# EP.net
KiCad netlist of a schematic drawn in Altium Designer
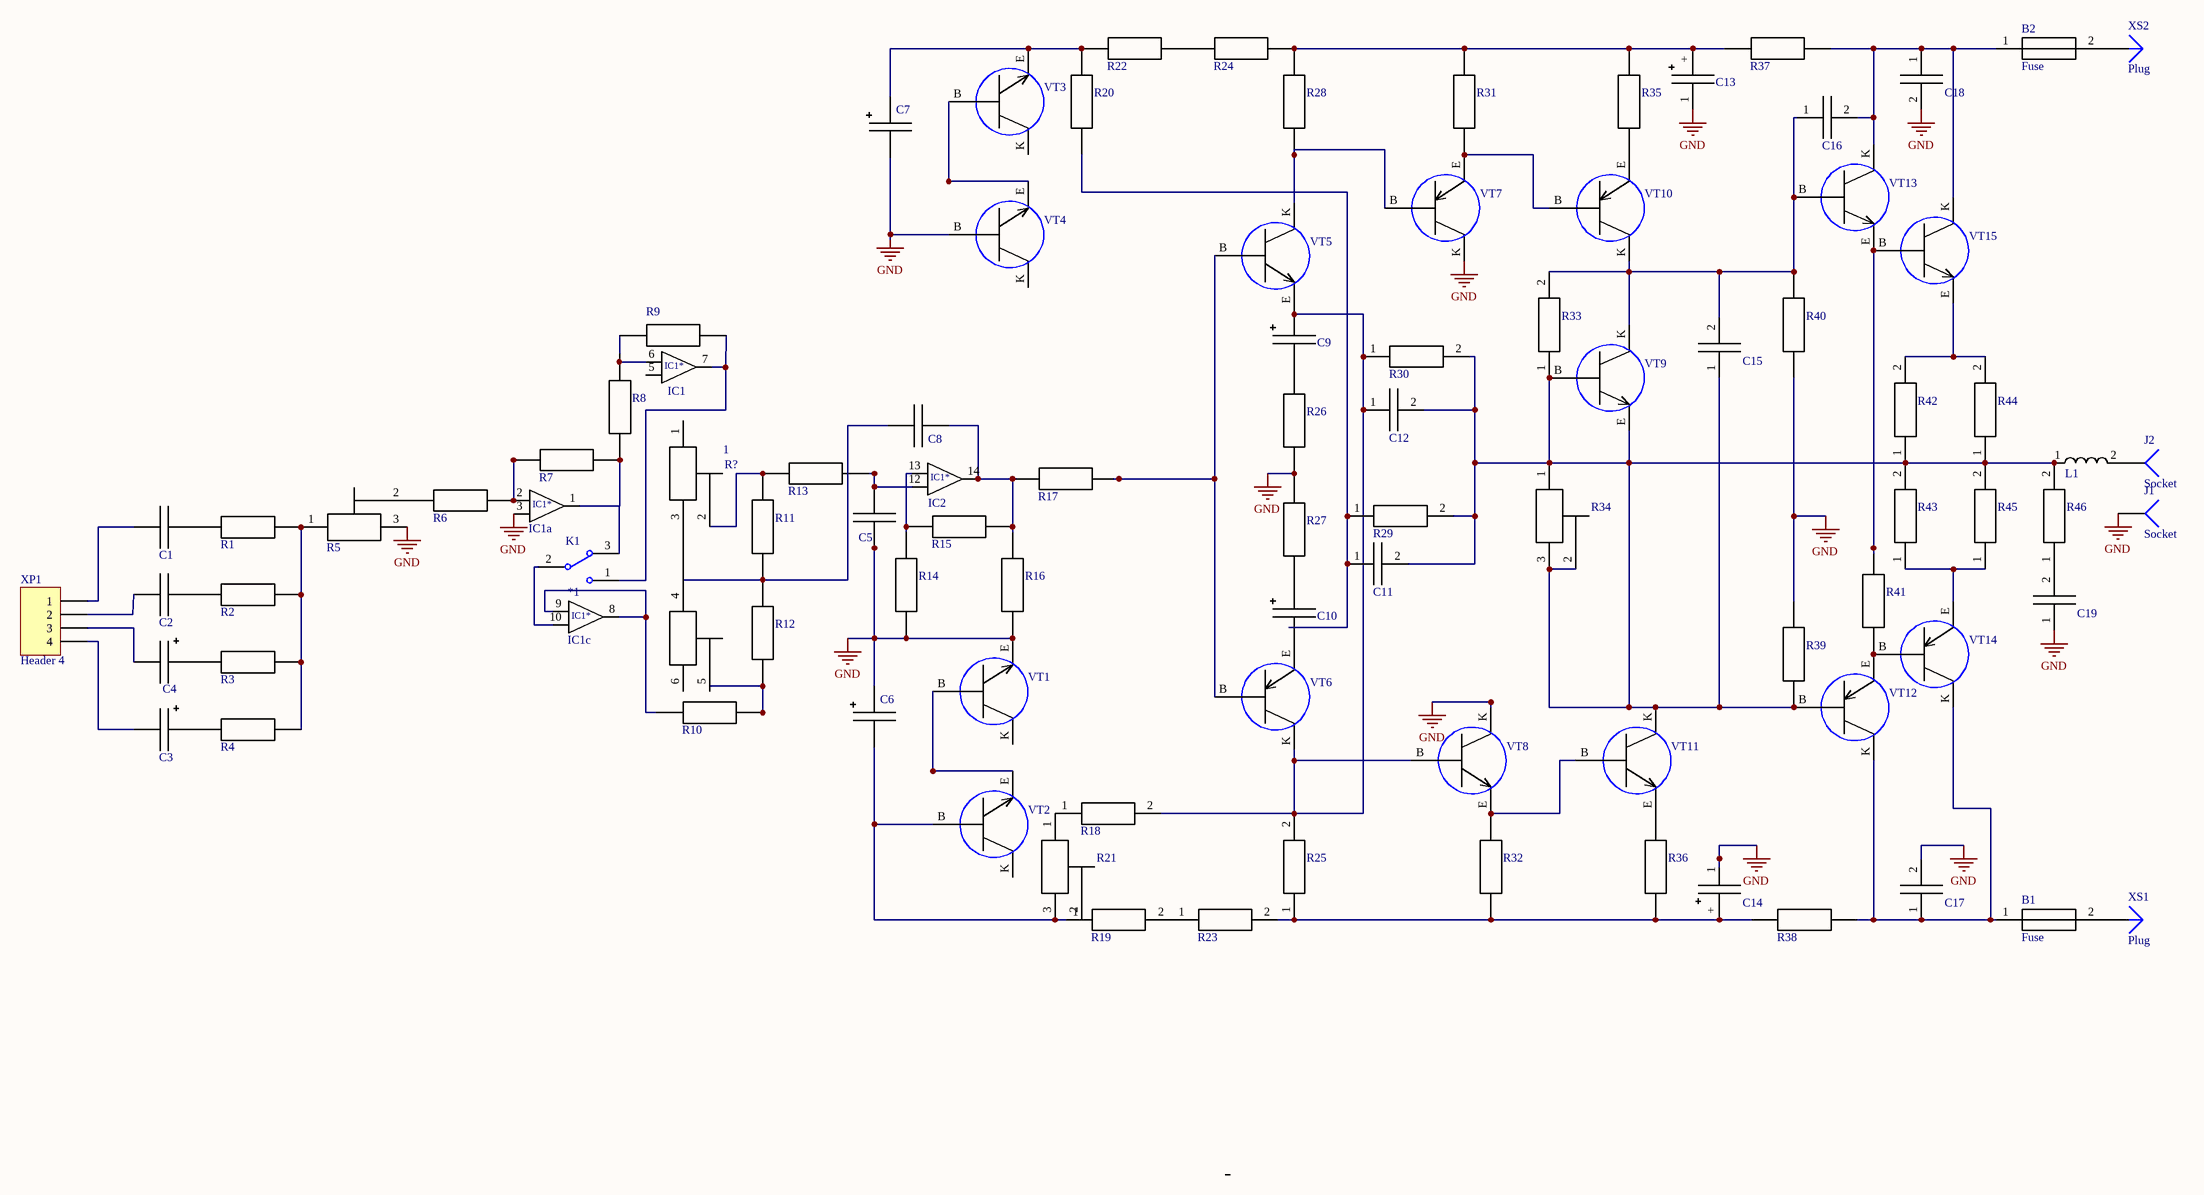
[diagram p0: EP.SchDoc]

(export (version "E")
  (design (tool "Eeschema 10.0.6"))
  (components
    (comp (ref "*1") (value "IC1c") (footprint "DIP8") (libsource (lib "Schlib2") (part "TL084")))
    (comp (ref "1")
      (value "R?")
      (footprint "PcbLib2:Pidresistor")
      (libsource (lib "Schlib2") (part "Pidres_2"))
    )
    (comp (ref "B1") (value "Fuse") (libsource (lib "Schlib2") (part "Fuse")))
    (comp (ref "B2") (value "Fuse") (libsource (lib "Schlib2") (part "Fuse")))
    (comp (ref "C1") (value "Capacitor") (footprint "Capacitor") (libsource (lib "") (part "Capacitor_1")))
    (comp (ref "C2") (value "Capacitor") (footprint "Capacitor") (libsource (lib "") (part "Capacitor_1")))
    (comp (ref "C3")
      (value "Capacitor (+)")
      (footprint "Capacitor (+) 2.5")
      (libsource (lib "Schlib2") (part "Capacitor (+)"))
    )
    (comp (ref "C4")
      (value "Capacitor (+)")
      (footprint "Capacitor (+) 2.5")
      (libsource (lib "Schlib2") (part "Capacitor (+)"))
    )
    (comp (ref "C5") (value "Capacitor") (footprint "Capacitor") (libsource (lib "") (part "Capacitor_1")))
    (comp (ref "C6")
      (value "Capacitor (+)")
      (footprint "Capacitor (+) 2.5")
      (libsource (lib "Schlib2") (part "Capacitor (+)"))
    )
    (comp (ref "C7")
      (value "Capacitor (+)")
      (footprint "Capacitor (+) 2.5")
      (libsource (lib "Schlib2") (part "Capacitor (+)"))
    )
    (comp (ref "C8") (value "Capacitor") (footprint "Capacitor") (libsource (lib "") (part "Capacitor_1")))
    (comp (ref "C9")
      (value "Capacitor (+)")
      (footprint "Capacitor (+) 2.5")
      (libsource (lib "Schlib2") (part "Capacitor (+)"))
    )
    (comp (ref "C10")
      (value "Capacitor (+)")
      (footprint "Capacitor (+) 2.5")
      (libsource (lib "Schlib2") (part "Capacitor (+)"))
    )
    (comp (ref "C11")
      (value "Capacitor")
      (footprint "Capacitor")
      (libsource (lib "Schlib2") (part "Capacitor"))
    )
    (comp (ref "C12")
      (value "Capacitor")
      (footprint "Capacitor")
      (libsource (lib "Schlib2") (part "Capacitor"))
    )
    (comp (ref "C13")
      (value "Capacitor (+)")
      (footprint "Capacitor (+) 2.5")
      (libsource (lib "") (part "Capacitor (+)_1"))
    )
    (comp (ref "C14")
      (value "Capacitor (+)")
      (footprint "Capacitor (+) 2.5")
      (libsource (lib "") (part "Capacitor (+)_1"))
    )
    (comp (ref "C15")
      (value "Capacitor")
      (footprint "Capacitor")
      (libsource (lib "Schlib2") (part "Capacitor"))
    )
    (comp (ref "C16")
      (value "Capacitor")
      (footprint "Capacitor")
      (libsource (lib "Schlib2") (part "Capacitor"))
    )
    (comp (ref "C17")
      (value "Capacitor")
      (footprint "Capacitor")
      (libsource (lib "Schlib2") (part "Capacitor"))
    )
    (comp (ref "C18")
      (value "Capacitor")
      (footprint "Capacitor")
      (libsource (lib "Schlib2") (part "Capacitor"))
    )
    (comp (ref "C19")
      (value "Capacitor")
      (footprint "Capacitor")
      (libsource (lib "Schlib2") (part "Capacitor"))
    )
    (comp (ref "IC1") (value "TL084") (footprint "DIP8") (libsource (lib "") (part "TL084_3")))
    (comp (ref "IC1a") (value "IC1a") (footprint "DIP8") (libsource (lib "") (part "TL084_2")))
    (comp (ref "IC2") (value "IC1d") (footprint "DIP8") (libsource (lib "") (part "TL084_1")))
    (comp (ref "J1")
      (value "Socket")
      (footprint "PIN1")
      (fields (field (name "PUBLISHER") "Altium Limited"))
      (libsource (lib "Miscellaneous Connectors") (part "Socket"))
    )
    (comp (ref "J2")
      (value "Socket")
      (footprint "PIN1")
      (fields (field (name "PUBLISHER") "Altium Limited"))
      (libsource (lib "Miscellaneous Connectors") (part "Socket"))
    )
    (comp (ref "K1")
      (value "K")
      (footprint "TL36WW15050")
      (description "SPDT Subminiature Toggle Switch, Right Angle Mounting, Vertical Actuation")
      (fields (field (name "PUBLISHER") "Altium Limited"))
      (libsource (lib "Miscellaneous Devices") (part "SW-SPDT"))
    )
    (comp (ref "L1") (value "Drosel") (footprint "Drosel") (libsource (lib "Schlib2") (part "Drosel")))
    (comp (ref "R1") (value "Resistor") (footprint "Resistor") (libsource (lib "Schlib2") (part "Resistor")))
    (comp (ref "R2") (value "Resistor") (footprint "Resistor") (libsource (lib "Schlib2") (part "Resistor")))
    (comp (ref "R3") (value "Resistor") (footprint "Resistor") (libsource (lib "Schlib2") (part "Resistor")))
    (comp (ref "R4") (value "Resistor") (footprint "Resistor") (libsource (lib "Schlib2") (part "Resistor")))
    (comp (ref "R5")
      (value "Pidresistor")
      (footprint "Pidrest_2")
      (libsource (lib "Schlib2") (part "Pidresistor"))
    )
    (comp (ref "R6") (value "Resistor") (footprint "Resistor") (libsource (lib "Schlib2") (part "Resistor")))
    (comp (ref "R7") (value "Resistor") (footprint "Resistor") (libsource (lib "Schlib2") (part "Resistor")))
    (comp (ref "R8") (value "Resistor") (footprint "Resistor") (libsource (lib "Schlib2") (part "Resistor")))
    (comp (ref "R9") (value "Resistor") (footprint "Resistor") (libsource (lib "Schlib2") (part "Resistor")))
    (comp (ref "R10") (value "Resistor") (footprint "Resistor") (libsource (lib "Schlib2") (part "Resistor")))
    (comp (ref "R11") (value "Resistor") (footprint "Resistor") (libsource (lib "Schlib2") (part "Resistor")))
    (comp (ref "R12") (value "Resistor") (footprint "Resistor") (libsource (lib "Schlib2") (part "Resistor")))
    (comp (ref "R13") (value "Resistor") (footprint "Resistor") (libsource (lib "Schlib2") (part "Resistor")))
    (comp (ref "R14") (value "Resistor") (footprint "Resistor") (libsource (lib "Schlib2") (part "Resistor")))
    (comp (ref "R15") (value "Resistor") (footprint "Resistor") (libsource (lib "Schlib2") (part "Resistor")))
    (comp (ref "R16") (value "Resistor") (footprint "Resistor") (libsource (lib "Schlib2") (part "Resistor")))
    (comp (ref "R17") (value "Resistor") (footprint "Resistor") (libsource (lib "Schlib2") (part "Resistor")))
    (comp (ref "R18") (value "Resistor") (footprint "Resistor") (libsource (lib "") (part "Resistor_1")))
    (comp (ref "R19") (value "Resistor") (footprint "Resistor") (libsource (lib "") (part "Resistor_1")))
    (comp (ref "R20") (value "Resistor") (footprint "Resistor") (libsource (lib "Schlib2") (part "Resistor")))
    (comp (ref "R21")
      (value "Pidresistor")
      (footprint "Pidresistor")
      (libsource (lib "Schlib2") (part "Pidresistor"))
    )
    (comp (ref "R22") (value "Resistor") (footprint "Resistor") (libsource (lib "Schlib2") (part "Resistor")))
    (comp (ref "R23") (value "Resistor") (footprint "Resistor") (libsource (lib "") (part "Resistor_1")))
    (comp (ref "R24") (value "Resistor") (footprint "Resistor") (libsource (lib "Schlib2") (part "Resistor")))
    (comp (ref "R25") (value "Resistor") (footprint "Resistor") (libsource (lib "") (part "Resistor_1")))
    (comp (ref "R26") (value "Resistor") (footprint "Resistor") (libsource (lib "Schlib2") (part "Resistor")))
    (comp (ref "R27") (value "Resistor") (footprint "Resistor") (libsource (lib "Schlib2") (part "Resistor")))
    (comp (ref "R28") (value "Resistor") (footprint "Resistor") (libsource (lib "Schlib2") (part "Resistor")))
    (comp (ref "R29") (value "Resistor") (footprint "Resistor") (libsource (lib "") (part "Resistor_1")))
    (comp (ref "R30") (value "Resistor") (footprint "Resistor") (libsource (lib "") (part "Resistor_1")))
    (comp (ref "R31") (value "Resistor") (footprint "Resistor") (libsource (lib "Schlib2") (part "Resistor")))
    (comp (ref "R32") (value "Resistor") (footprint "Resistor") (libsource (lib "Schlib2") (part "Resistor")))
    (comp (ref "R33") (value "Resistor") (footprint "Resistor") (libsource (lib "") (part "Resistor_1")))
    (comp (ref "R34")
      (value "Pidresistor")
      (footprint "Pidresistor")
      (libsource (lib "Schlib2") (part "Pidresistor"))
    )
    (comp (ref "R35") (value "Resistor") (footprint "Resistor") (libsource (lib "Schlib2") (part "Resistor")))
    (comp (ref "R36") (value "Resistor") (footprint "Resistor") (libsource (lib "Schlib2") (part "Resistor")))
    (comp (ref "R37") (value "Resistor") (footprint "Resistor") (libsource (lib "Schlib2") (part "Resistor")))
    (comp (ref "R38") (value "Resistor") (footprint "Resistor") (libsource (lib "Schlib2") (part "Resistor")))
    (comp (ref "R39") (value "Resistor") (footprint "Resistor") (libsource (lib "Schlib2") (part "Resistor")))
    (comp (ref "R40") (value "Resistor") (footprint "Resistor") (libsource (lib "Schlib2") (part "Resistor")))
    (comp (ref "R41") (value "Resistor") (footprint "Resistor") (libsource (lib "Schlib2") (part "Resistor")))
    (comp (ref "R42")
      (value "Resistor 1 Wt")
      (footprint "Resistor 1 Wt")
      (libsource (lib "Schlib2") (part "Resistor 1 Wt"))
    )
    (comp (ref "R43")
      (value "Resistor 1 Wt")
      (footprint "Resistor 1 Wt")
      (libsource (lib "Schlib2") (part "Resistor 1 Wt"))
    )
    (comp (ref "R44")
      (value "Resistor 1 Wt")
      (footprint "Resistor 1 Wt")
      (libsource (lib "Schlib2") (part "Resistor 1 Wt"))
    )
    (comp (ref "R45")
      (value "Resistor 1 Wt")
      (footprint "Resistor 1 Wt")
      (libsource (lib "Schlib2") (part "Resistor 1 Wt"))
    )
    (comp (ref "R46")
      (value "Resistor 1 Wt")
      (footprint "Resistor 1 Wt")
      (libsource (lib "Schlib2") (part "Resistor 1 Wt"))
    )
    (comp (ref "VT1") (value "卵238;639;") (footprint "TO-92") (libsource (lib "") (part "卵238;639;_1")))
    (comp (ref "VT2") (value "卵238;639;") (footprint "TO-92") (libsource (lib "") (part "卵238;639;_1")))
    (comp (ref "VT3") (value "卵238;639;") (footprint "TO-92") (libsource (lib "") (part "卵238;639;_1")))
    (comp (ref "VT4") (value "卵238;639;") (footprint "TO-92") (libsource (lib "") (part "卵238;639;_1")))
    (comp (ref "VT5") (value "卵238;639;") (footprint "TO-92") (libsource (lib "Schlib2") (part "卵238;639;")))
    (comp (ref "VT6") (value "卵640") (footprint "TO-92") (libsource (lib "Schlib2") (part "卵640")))
    (comp (ref "VT7") (value "卵640") (footprint "TO-92") (libsource (lib "Schlib2") (part "卵640")))
    (comp (ref "VT8") (value "卵238;639;") (footprint "TO-92") (libsource (lib "Schlib2") (part "卵238;639;")))
    (comp (ref "VT9")
      (value "MJE340")
      (footprint "TO-126(TO-225)")
      (libsource (lib "Schlib2") (part "MJE340"))
    )
    (comp (ref "VT10")
      (value "MJE350")
      (footprint "TO-126(TO-225)")
      (libsource (lib "Schlib2") (part "MJE350"))
    )
    (comp (ref "VT11")
      (value "BD137")
      (footprint "TO-126(TO-225)")
      (libsource (lib "Schlib2") (part "BD137"))
    )
    (comp (ref "VT12") (value "BD242C") (footprint "TO-220") (libsource (lib "Schlib2") (part "BD242C")))
    (comp (ref "VT13") (value "BD241C") (footprint "TO-220") (libsource (lib "Schlib2") (part "BD241C")))
    (comp (ref "VT14") (value "BD250C") (footprint "TO-220") (libsource (lib "Schlib2") (part "BD250C")))
    (comp (ref "VT15") (value "BD249C") (footprint "SOT-93") (libsource (lib "Schlib2") (part "BD249C")))
    (comp (ref "XP1")
      (value "Header 4")
      (footprint "HDR1X4")
      (description "Header, 4-Pin")
      (fields (field (name "PUBLISHER") "Altium Limited"))
      (libsource (lib "Miscellaneous Connectors") (part "Header 4"))
    )
    (comp (ref "XS1")
      (value "Plug")
      (footprint "PIN1")
      (fields (field (name "PUBLISHER") "Altium Limited"))
      (libsource (lib "Miscellaneous Connectors") (part "Plug"))
    )
    (comp (ref "XS2")
      (value "Plug")
      (footprint "PIN1")
      (fields (field (name "PUBLISHER") "Altium Limited"))
      (libsource (lib "Miscellaneous Connectors") (part "Plug"))
    )
  )
  (nets
    (net (code "1") (name "GND") (class "Default")
      (node (ref "C13") (pin "1") (pinfunction "1_1") (pintype "passive"))
      (node (ref "C14") (pin "1") (pinfunction "1_1") (pintype "passive"))
      (node (ref "C17") (pin "2") (pinfunction "2_2") (pintype "passive"))
      (node (ref "C18") (pin "2") (pinfunction "2_2") (pintype "passive"))
      (node (ref "C19") (pin "1") (pinfunction "1_1") (pintype "passive"))
      (node (ref "C5") (pin "2") (pinfunction "2_2") (pintype "passive"))
      (node (ref "C6") (pin "+") (pinfunction "+_+") (pintype "passive"))
      (node (ref "C7") (pin "1") (pinfunction "1_1") (pintype "passive"))
      (node (ref "IC1a") (pin "3") (pinfunction "3_3") (pintype "passive"))
      (node (ref "J1") (pin "1") (pinfunction "1_1") (pintype "passive"))
      (node (ref "R14") (pin "2") (pinfunction "2_2") (pintype "passive"))
      (node (ref "R16") (pin "2") (pinfunction "2_2") (pintype "passive"))
      (node (ref "R26") (pin "2") (pinfunction "2_2") (pintype "passive"))
      (node (ref "R27") (pin "1") (pinfunction "1_1") (pintype "passive"))
      (node (ref "R39") (pin "1") (pinfunction "1_1") (pintype "passive"))
      (node (ref "R40") (pin "2") (pinfunction "2_2") (pintype "passive"))
      (node (ref "R5") (pin "3") (pinfunction "3_3") (pintype "passive"))
      (node (ref "VT1") (pin "E") (pinfunction "E_E") (pintype "passive"))
      (node (ref "VT4") (pin "B") (pinfunction "B_B") (pintype "passive"))
      (node (ref "VT7") (pin "K") (pinfunction "K_K") (pintype "passive"))
      (node (ref "VT8") (pin "K") (pinfunction "K_K") (pintype "passive"))
    )
    (net (code "2") (name "Net-(*1-Pad8)") (class "Default")
      (node (ref "*1") (pin "8") (pinfunction "8_8") (pintype "passive"))
      (node (ref "*1") (pin "9") (pinfunction "9_9") (pintype "passive"))
      (node (ref "R10") (pin "1") (pinfunction "1_1") (pintype "passive"))
    )
    (net (code "3") (name "Net-(*1-Pad10)") (class "Default")
      (node (ref "*1") (pin "10") (pinfunction "10_10") (pintype "passive"))
      (node (ref "K1") (pin "2") (pinfunction "2_2") (pintype "passive"))
    )
    (net (code "4") (name "Net-(1-Pad2)") (class "Default")
      (node (ref "1") (pin "2") (pinfunction "2_2") (pintype "passive"))
      (node (ref "R11") (pin "1") (pinfunction "1_1") (pintype "passive"))
      (node (ref "R13") (pin "1") (pinfunction "1_1") (pintype "passive"))
    )
    (net (code "5") (name "Net-(B1-Pad1)") (class "Default")
      (node (ref "B1") (pin "1") (pinfunction "1_1") (pintype "passive"))
      (node (ref "C17") (pin "1") (pinfunction "1_1") (pintype "passive"))
      (node (ref "R38") (pin "1") (pinfunction "1_1") (pintype "passive"))
      (node (ref "VT12") (pin "K") (pinfunction "K_K") (pintype "passive"))
      (node (ref "VT14") (pin "K") (pinfunction "K_K") (pintype "passive"))
    )
    (net (code "6") (name "Net-(B1-Pad2)") (class "Default")
      (node (ref "B1") (pin "2") (pinfunction "2_2") (pintype "passive"))
      (node (ref "XS1") (pin "1") (pinfunction "1_1") (pintype "passive"))
    )
    (net (code "7") (name "Net-(B2-Pad1)") (class "Default")
      (node (ref "B2") (pin "1") (pinfunction "1_1") (pintype "passive"))
      (node (ref "C16") (pin "2") (pinfunction "2_2") (pintype "passive"))
      (node (ref "C18") (pin "1") (pinfunction "1_1") (pintype "passive"))
      (node (ref "R37") (pin "1") (pinfunction "1_1") (pintype "passive"))
      (node (ref "VT13") (pin "K") (pinfunction "K_K") (pintype "passive"))
      (node (ref "VT15") (pin "K") (pinfunction "K_K") (pintype "passive"))
    )
    (net (code "8") (name "Net-(B2-Pad2)") (class "Default")
      (node (ref "B2") (pin "2") (pinfunction "2_2") (pintype "passive"))
      (node (ref "XS2") (pin "1") (pinfunction "1_1") (pintype "passive"))
    )
    (net (code "9") (name "Net-(C1-Pad1)") (class "Default")
      (node (ref "C1") (pin "1") (pinfunction "1_1") (pintype "passive"))
      (node (ref "XP1") (pin "1") (pinfunction "1_1") (pintype "passive"))
    )
    (net (code "10") (name "Net-(C1-Pad2)") (class "Default")
      (node (ref "C1") (pin "2") (pinfunction "2_2") (pintype "passive"))
      (node (ref "R1") (pin "1") (pinfunction "1_1") (pintype "passive"))
    )
    (net (code "11") (name "Net-(C2-Pad1)") (class "Default")
      (node (ref "C2") (pin "1") (pinfunction "1_1") (pintype "passive"))
      (node (ref "XP1") (pin "2") (pinfunction "2_2") (pintype "passive"))
    )
    (net (code "12") (name "Net-(C2-Pad2)") (class "Default")
      (node (ref "C2") (pin "2") (pinfunction "2_2") (pintype "passive"))
      (node (ref "R2") (pin "1") (pinfunction "1_1") (pintype "passive"))
    )
    (net (code "13") (name "Net-(C3-Pad+)") (class "Default")
      (node (ref "C3") (pin "+") (pinfunction "+_+") (pintype "passive"))
      (node (ref "R4") (pin "1") (pinfunction "1_1") (pintype "passive"))
    )
    (net (code "14") (name "Net-(C3-Pad1)") (class "Default")
      (node (ref "C3") (pin "1") (pinfunction "1_1") (pintype "passive"))
      (node (ref "XP1") (pin "4") (pinfunction "4_4") (pintype "passive"))
    )
    (net (code "15") (name "Net-(C4-Pad+)") (class "Default")
      (node (ref "C4") (pin "+") (pinfunction "+_+") (pintype "passive"))
      (node (ref "R3") (pin "1") (pinfunction "1_1") (pintype "passive"))
    )
    (net (code "16") (name "Net-(C4-Pad1)") (class "Default")
      (node (ref "C4") (pin "1") (pinfunction "1_1") (pintype "passive"))
      (node (ref "XP1") (pin "3") (pinfunction "3_3") (pintype "passive"))
    )
    (net (code "17") (name "Net-(C5-Pad1)") (class "Default")
      (node (ref "C5") (pin "1") (pinfunction "1_1") (pintype "passive"))
      (node (ref "IC2") (pin "12") (pinfunction "12_12") (pintype "passive"))
      (node (ref "R13") (pin "2") (pinfunction "2_2") (pintype "passive"))
    )
    (net (code "18") (name "Net-(C6-Pad1)") (class "Default")
      (node (ref "C6") (pin "1") (pinfunction "1_1") (pintype "passive"))
      (node (ref "VT2") (pin "B") (pinfunction "B_B") (pintype "passive"))
    )
    (net (code "19") (name "Net-(C7-Pad+)") (class "Default")
      (node (ref "C7") (pin "+") (pinfunction "+_+") (pintype "passive"))
      (node (ref "R20") (pin "2") (pinfunction "2_2") (pintype "passive"))
      (node (ref "R22") (pin "1") (pinfunction "1_1") (pintype "passive"))
      (node (ref "VT3") (pin "E") (pinfunction "E_E") (pintype "passive"))
    )
    (net (code "20") (name "Net-(C8-Pad1)") (class "Default")
      (node (ref "C8") (pin "1") (pinfunction "1_1") (pintype "passive"))
      (node (ref "R11") (pin "2") (pinfunction "2_2") (pintype "passive"))
      (node (ref "R12") (pin "1") (pinfunction "1_1") (pintype "passive"))
    )
    (net (code "21") (name "Net-(C8-Pad2)") (class "Default")
      (node (ref "C8") (pin "2") (pinfunction "2_2") (pintype "passive"))
      (node (ref "IC2") (pin "14") (pinfunction "14_14") (pintype "passive"))
      (node (ref "R15") (pin "2") (pinfunction "2_2") (pintype "passive"))
      (node (ref "R16") (pin "1") (pinfunction "1_1") (pintype "passive"))
      (node (ref "R17") (pin "1") (pinfunction "1_1") (pintype "passive"))
    )
    (net (code "22") (name "Net-(C9-Pad+)") (class "Default")
      (node (ref "C9") (pin "+") (pinfunction "+_+") (pintype "passive"))
      (node (ref "VT5") (pin "E") (pinfunction "E_E") (pintype "passive"))
    )
    (net (code "23") (name "Net-(C10-Pad+)") (class "Default")
      (node (ref "C10") (pin "+") (pinfunction "+_+") (pintype "passive"))
      (node (ref "R27") (pin "2") (pinfunction "2_2") (pintype "passive"))
    )
    (net (code "24") (name "Net-(C10-Pad1)") (class "Default")
      (node (ref "C10") (pin "1") (pinfunction "1_1") (pintype "passive"))
      (node (ref "VT6") (pin "E") (pinfunction "E_E") (pintype "passive"))
    )
    (net (code "25") (name "Net-(C11-Pad1)") (class "Default")
      (node (ref "C11") (pin "1") (pinfunction "1_1") (pintype "passive"))
      (node (ref "R20") (pin "1") (pinfunction "1_1") (pintype "passive"))
      (node (ref "R29") (pin "1") (pinfunction "1_1") (pintype "passive"))
    )
    (net (code "26") (name "Net-(C11-Pad2)") (class "Default")
      (node (ref "C11") (pin "2") (pinfunction "2_2") (pintype "passive"))
      (node (ref "C12") (pin "2") (pinfunction "2_2") (pintype "passive"))
      (node (ref "C15") (pin "1") (pinfunction "1_1") (pintype "passive"))
      (node (ref "L1") (pin "1") (pinfunction "1_1") (pintype "passive"))
      (node (ref "R29") (pin "2") (pinfunction "2_2") (pintype "passive"))
      (node (ref "R30") (pin "2") (pinfunction "2_2") (pintype "passive"))
      (node (ref "R33") (pin "1") (pinfunction "1_1") (pintype "passive"))
      (node (ref "R34") (pin "1") (pinfunction "1_1") (pintype "passive"))
      (node (ref "R34") (pin "2") (pinfunction "2_2") (pintype "passive"))
      (node (ref "R34") (pin "3") (pinfunction "3_3") (pintype "passive"))
      (node (ref "R39") (pin "2") (pinfunction "2_2") (pintype "passive"))
      (node (ref "R42") (pin "1") (pinfunction "1_1") (pintype "passive"))
      (node (ref "R43") (pin "2") (pinfunction "2_2") (pintype "passive"))
      (node (ref "R44") (pin "1") (pinfunction "1_1") (pintype "passive"))
      (node (ref "R45") (pin "2") (pinfunction "2_2") (pintype "passive"))
      (node (ref "R46") (pin "2") (pinfunction "2_2") (pintype "passive"))
      (node (ref "VT11") (pin "K") (pinfunction "K_K") (pintype "passive"))
      (node (ref "VT12") (pin "B") (pinfunction "B_B") (pintype "passive"))
      (node (ref "VT9") (pin "B") (pinfunction "B_B") (pintype "passive"))
      (node (ref "VT9") (pin "E") (pinfunction "E_E") (pintype "passive"))
    )
    (net (code "27") (name "Net-(C12-Pad1)") (class "Default")
      (node (ref "C12") (pin "1") (pinfunction "1_1") (pintype "passive"))
      (node (ref "R18") (pin "2") (pinfunction "2_2") (pintype "passive"))
      (node (ref "R25") (pin "2") (pinfunction "2_2") (pintype "passive"))
      (node (ref "R30") (pin "1") (pinfunction "1_1") (pintype "passive"))
      (node (ref "VT6") (pin "K") (pinfunction "K_K") (pintype "passive"))
      (node (ref "VT8") (pin "B") (pinfunction "B_B") (pintype "passive"))
    )
    (net (code "28") (name "Net-(C13-Pad+)") (class "Default")
      (node (ref "C13") (pin "+") (pinfunction "+_+") (pintype "passive"))
      (node (ref "R24") (pin "2") (pinfunction "2_2") (pintype "passive"))
      (node (ref "R28") (pin "1") (pinfunction "1_1") (pintype "passive"))
      (node (ref "R31") (pin "1") (pinfunction "1_1") (pintype "passive"))
      (node (ref "R35") (pin "1") (pinfunction "1_1") (pintype "passive"))
      (node (ref "R37") (pin "2") (pinfunction "2_2") (pintype "passive"))
    )
    (net (code "29") (name "Net-(C14-Pad+)") (class "Default")
      (node (ref "C14") (pin "+") (pinfunction "+_+") (pintype "passive"))
      (node (ref "R23") (pin "2") (pinfunction "2_2") (pintype "passive"))
      (node (ref "R25") (pin "1") (pinfunction "1_1") (pintype "passive"))
      (node (ref "R32") (pin "1") (pinfunction "1_1") (pintype "passive"))
      (node (ref "R36") (pin "1") (pinfunction "1_1") (pintype "passive"))
      (node (ref "R38") (pin "2") (pinfunction "2_2") (pintype "passive"))
    )
    (net (code "30") (name "Net-(C15-Pad2)") (class "Default")
      (node (ref "C15") (pin "2") (pinfunction "2_2") (pintype "passive"))
      (node (ref "C16") (pin "1") (pinfunction "1_1") (pintype "passive"))
      (node (ref "R33") (pin "2") (pinfunction "2_2") (pintype "passive"))
      (node (ref "R40") (pin "1") (pinfunction "1_1") (pintype "passive"))
      (node (ref "VT10") (pin "K") (pinfunction "K_K") (pintype "passive"))
      (node (ref "VT13") (pin "B") (pinfunction "B_B") (pintype "passive"))
      (node (ref "VT9") (pin "K") (pinfunction "K_K") (pintype "passive"))
    )
    (net (code "31") (name "Net-(C19-Pad2)") (class "Default")
      (node (ref "C19") (pin "2") (pinfunction "2_2") (pintype "passive"))
      (node (ref "R46") (pin "1") (pinfunction "1_1") (pintype "passive"))
    )
    (net (code "32") (name "Net-(IC1-Pad7)") (class "Default")
      (node (ref "IC1") (pin "7") (pinfunction "7_7") (pintype "passive"))
      (node (ref "K1") (pin "1") (pinfunction "1_1") (pintype "passive"))
      (node (ref "R9") (pin "2") (pinfunction "2_2") (pintype "passive"))
    )
    (net (code "33") (name "Net-(IC1a-Pad1)") (class "Default")
      (node (ref "IC1a") (pin "1") (pinfunction "1_1") (pintype "passive"))
      (node (ref "K1") (pin "3") (pinfunction "3_3") (pintype "passive"))
    )
    (net (code "34") (name "Net-(IC1a-Pad2)") (class "Default")
      (node (ref "IC1a") (pin "2") (pinfunction "2_2") (pintype "passive"))
      (node (ref "R6") (pin "2") (pinfunction "2_2") (pintype "passive"))
      (node (ref "R7") (pin "1") (pinfunction "1_1") (pintype "passive"))
    )
    (net (code "35") (name "Net-(IC2-Pad13)") (class "Default")
      (node (ref "IC2") (pin "13") (pinfunction "13_13") (pintype "passive"))
      (node (ref "R14") (pin "1") (pinfunction "1_1") (pintype "passive"))
      (node (ref "R15") (pin "1") (pinfunction "1_1") (pintype "passive"))
    )
    (net (code "36") (name "Net-(J2-Pad1)") (class "Default")
      (node (ref "J2") (pin "1") (pinfunction "1_1") (pintype "passive"))
      (node (ref "L1") (pin "2") (pinfunction "2_2") (pintype "passive"))
    )
    (net (code "37") (name "Net-(R1-Pad2)") (class "Default")
      (node (ref "R1") (pin "2") (pinfunction "2_2") (pintype "passive"))
      (node (ref "R2") (pin "2") (pinfunction "2_2") (pintype "passive"))
      (node (ref "R3") (pin "2") (pinfunction "2_2") (pintype "passive"))
      (node (ref "R4") (pin "2") (pinfunction "2_2") (pintype "passive"))
      (node (ref "R5") (pin "1") (pinfunction "1_1") (pintype "passive"))
    )
    (net (code "38") (name "Net-(R5-Pad2)") (class "Default")
      (node (ref "R5") (pin "2") (pinfunction "2_2") (pintype "passive"))
      (node (ref "R6") (pin "1") (pinfunction "1_1") (pintype "passive"))
    )
    (net (code "39") (name "Net-(R7-Pad2)") (class "Default")
      (node (ref "R7") (pin "2") (pinfunction "2_2") (pintype "passive"))
      (node (ref "R8") (pin "2") (pinfunction "2_2") (pintype "passive"))
    )
    (net (code "40") (name "Net-(R8-Pad1)") (class "Default")
      (node (ref "R8") (pin "1") (pinfunction "1_1") (pintype "passive"))
      (node (ref "R9") (pin "1") (pinfunction "1_1") (pintype "passive"))
    )
    (net (code "41") (name "Net-(R10-Pad2)") (class "Default")
      (node (ref "R10") (pin "2") (pinfunction "2_2") (pintype "passive"))
      (node (ref "R12") (pin "2") (pinfunction "2_2") (pintype "passive"))
    )
    (net (code "42") (name "Net-(R17-Pad2)") (class "Default")
      (node (ref "R17") (pin "2") (pinfunction "2_2") (pintype "passive"))
      (node (ref "VT5") (pin "B") (pinfunction "B_B") (pintype "passive"))
      (node (ref "VT6") (pin "B") (pinfunction "B_B") (pintype "passive"))
    )
    (net (code "43") (name "Net-(R18-Pad1)") (class "Default")
      (node (ref "R18") (pin "1") (pinfunction "1_1") (pintype "passive"))
      (node (ref "R21") (pin "1") (pinfunction "1_1") (pintype "passive"))
    )
    (net (code "44") (name "Net-(R19-Pad1)") (class "Default")
      (node (ref "R19") (pin "1") (pinfunction "1_1") (pintype "passive"))
      (node (ref "R21") (pin "3") (pinfunction "3_3") (pintype "passive"))
    )
    (net (code "45") (name "Net-(R19-Pad2)") (class "Default")
      (node (ref "R19") (pin "2") (pinfunction "2_2") (pintype "passive"))
      (node (ref "R23") (pin "1") (pinfunction "1_1") (pintype "passive"))
    )
    (net (code "46") (name "Net-(R22-Pad2)") (class "Default")
      (node (ref "R22") (pin "2") (pinfunction "2_2") (pintype "passive"))
      (node (ref "R24") (pin "1") (pinfunction "1_1") (pintype "passive"))
    )
    (net (code "47") (name "Net-(R28-Pad2)") (class "Default")
      (node (ref "R28") (pin "2") (pinfunction "2_2") (pintype "passive"))
      (node (ref "VT5") (pin "K") (pinfunction "K_K") (pintype "passive"))
      (node (ref "VT7") (pin "B") (pinfunction "B_B") (pintype "passive"))
    )
    (net (code "48") (name "Net-(R31-Pad2)") (class "Default")
      (node (ref "R31") (pin "2") (pinfunction "2_2") (pintype "passive"))
      (node (ref "VT10") (pin "B") (pinfunction "B_B") (pintype "passive"))
      (node (ref "VT7") (pin "E") (pinfunction "E_E") (pintype "passive"))
    )
    (net (code "49") (name "Net-(R32-Pad2)") (class "Default")
      (node (ref "R32") (pin "2") (pinfunction "2_2") (pintype "passive"))
      (node (ref "VT11") (pin "B") (pinfunction "B_B") (pintype "passive"))
      (node (ref "VT8") (pin "E") (pinfunction "E_E") (pintype "passive"))
    )
    (net (code "50") (name "Net-(R35-Pad2)") (class "Default")
      (node (ref "R35") (pin "2") (pinfunction "2_2") (pintype "passive"))
      (node (ref "VT10") (pin "E") (pinfunction "E_E") (pintype "passive"))
    )
    (net (code "51") (name "Net-(R36-Pad2)") (class "Default")
      (node (ref "R36") (pin "2") (pinfunction "2_2") (pintype "passive"))
      (node (ref "VT11") (pin "E") (pinfunction "E_E") (pintype "passive"))
    )
    (net (code "52") (name "Net-(R41-Pad1)") (class "Default")
      (node (ref "R41") (pin "1") (pinfunction "1_1") (pintype "passive"))
      (node (ref "VT13") (pin "E") (pinfunction "E_E") (pintype "passive"))
      (node (ref "VT15") (pin "B") (pinfunction "B_B") (pintype "passive"))
    )
    (net (code "53") (name "Net-(R41-Pad2)") (class "Default")
      (node (ref "R41") (pin "2") (pinfunction "2_2") (pintype "passive"))
      (node (ref "VT12") (pin "E") (pinfunction "E_E") (pintype "passive"))
      (node (ref "VT14") (pin "B") (pinfunction "B_B") (pintype "passive"))
    )
    (net (code "54") (name "Net-(R42-Pad2)") (class "Default")
      (node (ref "R42") (pin "2") (pinfunction "2_2") (pintype "passive"))
      (node (ref "R44") (pin "2") (pinfunction "2_2") (pintype "passive"))
      (node (ref "VT15") (pin "E") (pinfunction "E_E") (pintype "passive"))
    )
    (net (code "55") (name "Net-(R43-Pad1)") (class "Default")
      (node (ref "R43") (pin "1") (pinfunction "1_1") (pintype "passive"))
      (node (ref "R45") (pin "1") (pinfunction "1_1") (pintype "passive"))
      (node (ref "VT14") (pin "E") (pinfunction "E_E") (pintype "passive"))
    )
    (net (code "56") (name "Net-(VT1-PadB)") (class "Default")
      (node (ref "VT1") (pin "B") (pinfunction "B_B") (pintype "passive"))
      (node (ref "VT2") (pin "E") (pinfunction "E_E") (pintype "passive"))
    )
    (net (code "57") (name "Net-(VT3-PadB)") (class "Default")
      (node (ref "VT3") (pin "B") (pinfunction "B_B") (pintype "passive"))
      (node (ref "VT4") (pin "E") (pinfunction "E_E") (pintype "passive"))
    )
    (net (code "58") (name "unconnected-(1-Pad1)") (class "Default")
      (node (ref "1") (pin "1") (pinfunction "1_1") (pintype "passive"))
    )
    (net (code "59") (name "unconnected-(1-Pad3)") (class "Default")
      (node (ref "1") (pin "3") (pinfunction "3_3") (pintype "passive"))
    )
    (net (code "60") (name "unconnected-(1-Pad4)") (class "Default")
      (node (ref "1") (pin "4") (pinfunction "4_4") (pintype "passive"))
    )
    (net (code "61") (name "unconnected-(1-Pad5)") (class "Default")
      (node (ref "1") (pin "5") (pinfunction "5_5") (pintype "passive"))
    )
    (net (code "62") (name "unconnected-(1-Pad6)") (class "Default")
      (node (ref "1") (pin "6") (pinfunction "6_6") (pintype "passive"))
    )
    (net (code "63") (name "unconnected-(C9-Pad1)") (class "Default")
      (node (ref "C9") (pin "1") (pinfunction "1_1") (pintype "passive"))
    )
    (net (code "64") (name "unconnected-(IC1-Pad5)") (class "Default")
      (node (ref "IC1") (pin "5") (pinfunction "5_5") (pintype "passive"))
    )
    (net (code "65") (name "unconnected-(IC1-Pad6)") (class "Default")
      (node (ref "IC1") (pin "6") (pinfunction "6_6") (pintype "passive"))
    )
    (net (code "66") (name "unconnected-(R21-Pad2)") (class "Default")
      (node (ref "R21") (pin "2") (pinfunction "2_2") (pintype "passive"))
    )
    (net (code "67") (name "unconnected-(R26-Pad1)") (class "Default")
      (node (ref "R26") (pin "1") (pinfunction "1_1") (pintype "passive"))
    )
    (net (code "68") (name "unconnected-(VT1-PadK)") (class "Default")
      (node (ref "VT1") (pin "K") (pinfunction "K_K") (pintype "passive"))
    )
    (net (code "69") (name "unconnected-(VT2-PadK)") (class "Default")
      (node (ref "VT2") (pin "K") (pinfunction "K_K") (pintype "passive"))
    )
    (net (code "70") (name "unconnected-(VT3-PadK)") (class "Default")
      (node (ref "VT3") (pin "K") (pinfunction "K_K") (pintype "passive"))
    )
    (net (code "71") (name "unconnected-(VT4-PadK)") (class "Default")
      (node (ref "VT4") (pin "K") (pinfunction "K_K") (pintype "passive"))
    )
  )
)
